# PIZ-II.net
KiCad netlist of a schematic drawn in EAGLE
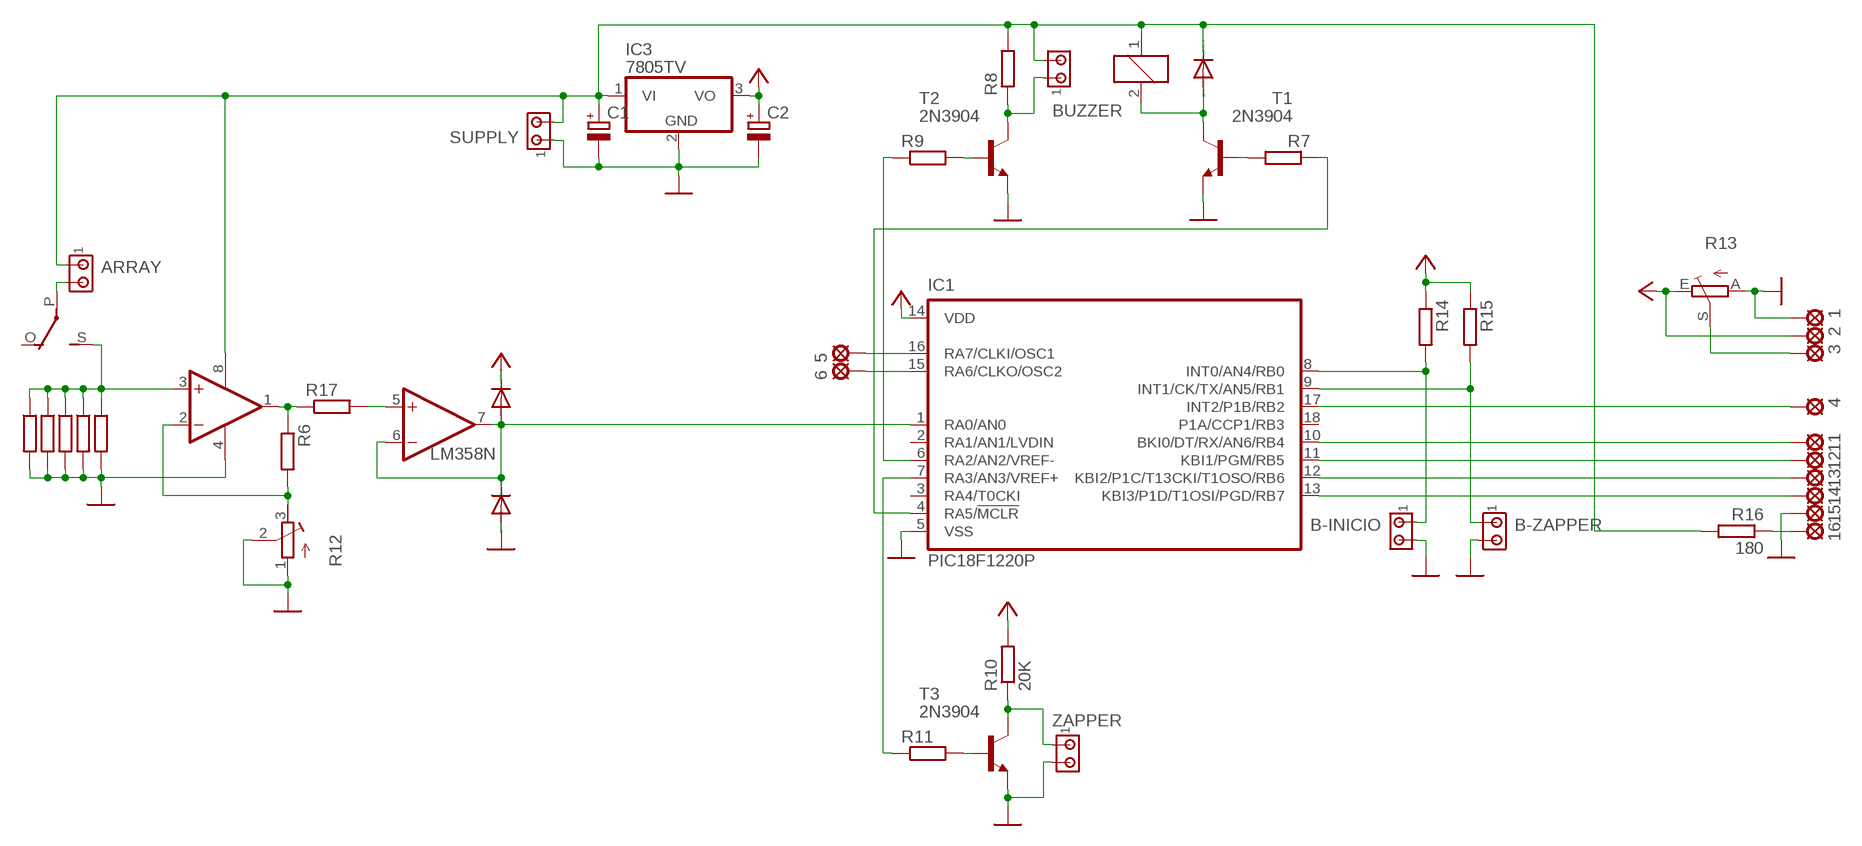
[diagram p0: schematic, sheet 1]

(export (version "E")
  (design (tool "Eeschema 10.0.6"))
  (components
    (comp (ref "1")
      (value "LSP10")
      (footprint "eagle-import:LSP10")
      (libsource (lib "eagle-import") (part "LSP10"))
    )
    (comp (ref "2")
      (value "LSP10")
      (footprint "eagle-import:LSP10")
      (libsource (lib "eagle-import") (part "LSP10"))
    )
    (comp (ref "3")
      (value "LSP10")
      (footprint "eagle-import:LSP10")
      (libsource (lib "eagle-import") (part "LSP10"))
    )
    (comp (ref "4")
      (value "LSP10")
      (footprint "eagle-import:LSP10")
      (libsource (lib "eagle-import") (part "LSP10"))
    )
    (comp (ref "5")
      (value "LSP10")
      (footprint "eagle-import:LSP10")
      (libsource (lib "eagle-import") (part "LSP10"))
    )
    (comp (ref "6")
      (value "LSP10")
      (footprint "eagle-import:LSP10")
      (libsource (lib "eagle-import") (part "LSP10"))
    )
    (comp (ref "11")
      (value "LSP10")
      (footprint "eagle-import:LSP10")
      (libsource (lib "eagle-import") (part "LSP10"))
    )
    (comp (ref "12")
      (value "LSP10")
      (footprint "eagle-import:LSP10")
      (libsource (lib "eagle-import") (part "LSP10"))
    )
    (comp (ref "13")
      (value "LSP10")
      (footprint "eagle-import:LSP10")
      (libsource (lib "eagle-import") (part "LSP10"))
    )
    (comp (ref "14")
      (value "LSP10")
      (footprint "eagle-import:LSP10")
      (libsource (lib "eagle-import") (part "LSP10"))
    )
    (comp (ref "15")
      (value "LSP10")
      (footprint "eagle-import:LSP10")
      (libsource (lib "eagle-import") (part "LSP10"))
    )
    (comp (ref "16")
      (value "LSP10")
      (footprint "eagle-import:LSP10")
      (libsource (lib "eagle-import") (part "LSP10"))
    )
    (comp (ref "ARRAY")
      (value "MTA02-100")
      (footprint "eagle-import:10X02MTA")
      (libsource (lib "eagle-import") (part "MTA02-100"))
    )
    (comp (ref "B-INICIO")
      (value "MTA02-100")
      (footprint "eagle-import:10X02MTA")
      (libsource (lib "eagle-import") (part "MTA02-100"))
    )
    (comp (ref "B-ZAPPER")
      (value "MTA02-100")
      (footprint "eagle-import:10X02MTA")
      (libsource (lib "eagle-import") (part "MTA02-100"))
    )
    (comp (ref "BUZZER")
      (value "MTA02-100")
      (footprint "eagle-import:10X02MTA")
      (libsource (lib "eagle-import") (part "MTA02-100"))
    )
    (comp (ref "C1")
      (value "CPOL-EUE2.5-7")
      (footprint "eagle-import:E2,5-7")
      (libsource (lib "eagle-import") (part "CPOL-EUE2.5-7"))
    )
    (comp (ref "C2")
      (value "CPOL-EUE2.5-7")
      (footprint "eagle-import:E2,5-7")
      (libsource (lib "eagle-import") (part "CPOL-EUE2.5-7"))
    )
    (comp (ref "D1")
      (value "1N4148DO35-7")
      (footprint "eagle-import:DO35-7")
      (libsource (lib "eagle-import") (part "1N4148DO35-7"))
    )
    (comp (ref "D2")
      (value "1N4148DO35-7")
      (footprint "eagle-import:DO35-7")
      (libsource (lib "eagle-import") (part "1N4148DO35-7"))
    )
    (comp (ref "D3")
      (value "1N4148DO35-7")
      (footprint "eagle-import:DO35-7")
      (libsource (lib "eagle-import") (part "1N4148DO35-7"))
    )
    (comp (ref "IC1")
      (value "PIC18F1220P")
      (footprint "eagle-import:DIL18")
      (fields (field (name "MF") "MICROCHIP") (field (name "MPN") "PIC18F1220-I/P"))
      (libsource (lib "eagle-import") (part "PIC18F120P2"))
    )
    (comp (ref "IC2")
      (value "LM358N")
      (footprint "eagle-import:DIL08")
      (libsource (lib "eagle-import") (part "LM358N"))
    )
    (comp (ref "IC3")
      (value "7805TV")
      (footprint "eagle-import:TO220V")
      (libsource (lib "eagle-import") (part "78TV05"))
    )
    (comp (ref "K1")
      (value "G5L")
      (footprint "eagle-import:G5LE")
      (libsource (lib "eagle-import") (part "G5L"))
    )
    (comp (ref "R1")
      (value "R-EU_0204/7")
      (footprint "eagle-import:0204_7")
      (libsource (lib "eagle-import") (part "R-EU_0204/7"))
    )
    (comp (ref "R2")
      (value "R-EU_0204/7")
      (footprint "eagle-import:0204_7")
      (libsource (lib "eagle-import") (part "R-EU_0204/7"))
    )
    (comp (ref "R3")
      (value "R-EU_0204/7")
      (footprint "eagle-import:0204_7")
      (libsource (lib "eagle-import") (part "R-EU_0204/7"))
    )
    (comp (ref "R4")
      (value "R-EU_0204/7")
      (footprint "eagle-import:0204_7")
      (libsource (lib "eagle-import") (part "R-EU_0204/7"))
    )
    (comp (ref "R5")
      (value "R-EU_0204/7")
      (footprint "eagle-import:0204_7")
      (libsource (lib "eagle-import") (part "R-EU_0204/7"))
    )
    (comp (ref "R6")
      (value "R-EU_0204/7")
      (footprint "eagle-import:0204_7")
      (libsource (lib "eagle-import") (part "R-EU_0204/7"))
    )
    (comp (ref "R7")
      (value "R-EU_0204/7")
      (footprint "eagle-import:0204_7")
      (libsource (lib "eagle-import") (part "R-EU_0204/7"))
    )
    (comp (ref "R8")
      (value "R-EU_0204/7")
      (footprint "eagle-import:0204_7")
      (libsource (lib "eagle-import") (part "R-EU_0204/7"))
    )
    (comp (ref "R9")
      (value "R-EU_0204/7")
      (footprint "eagle-import:0204_7")
      (libsource (lib "eagle-import") (part "R-EU_0204/7"))
    )
    (comp (ref "R10")
      (value "20K")
      (footprint "eagle-import:0204_7")
      (libsource (lib "eagle-import") (part "R-EU_0204/7"))
    )
    (comp (ref "R11")
      (value "R-EU_0204/7")
      (footprint "eagle-import:0204_7")
      (libsource (lib "eagle-import") (part "R-EU_0204/7"))
    )
    (comp (ref "R12")
      (value "R-TRIMM64W")
      (footprint "eagle-import:RTRIM64W")
      (libsource (lib "eagle-import") (part "R-TRIMM64W"))
    )
    (comp (ref "R13")
      (value "TRIM_EU-CA6V")
      (footprint "eagle-import:CA6V")
      (libsource (lib "eagle-import") (part "TRIM_EU-CA6V"))
    )
    (comp (ref "R14")
      (value "R-EU_0204/7")
      (footprint "eagle-import:0204_7")
      (libsource (lib "eagle-import") (part "R-EU_0204/7"))
    )
    (comp (ref "R15")
      (value "R-EU_0204/7")
      (footprint "eagle-import:0204_7")
      (libsource (lib "eagle-import") (part "R-EU_0204/7"))
    )
    (comp (ref "R16")
      (value "180")
      (footprint "eagle-import:0204_7")
      (libsource (lib "eagle-import") (part "R-EU_0204/7"))
    )
    (comp (ref "R17")
      (value "R-EU_0204/7")
      (footprint "eagle-import:0204_7")
      (libsource (lib "eagle-import") (part "R-EU_0204/7"))
    )
    (comp (ref "SUPPLY")
      (value "MTA02-100")
      (footprint "eagle-import:10X02MTA")
      (libsource (lib "eagle-import") (part "MTA02-100"))
    )
    (comp (ref "T1")
      (value "2N3904")
      (footprint "eagle-import:TO92")
      (libsource (lib "eagle-import") (part "2N3904"))
    )
    (comp (ref "T2")
      (value "2N3904")
      (footprint "eagle-import:TO92")
      (libsource (lib "eagle-import") (part "2N3904"))
    )
    (comp (ref "T3")
      (value "2N3904")
      (footprint "eagle-import:TO92")
      (libsource (lib "eagle-import") (part "2N3904"))
    )
    (comp (ref "ZAPPER")
      (value "MTA02-100")
      (footprint "eagle-import:10X02MTA")
      (libsource (lib "eagle-import") (part "MTA02-100"))
    )
  )
  (nets
    (net (code "1") (name "GND") (class "Default")
      (node (ref "1") (pin "MP") (pinfunction "MP_MP") (pintype "passive"))
      (node (ref "15") (pin "MP") (pinfunction "MP_MP") (pintype "passive"))
      (node (ref "B-INICIO") (pin "2") (pinfunction "2_2") (pintype "passive"))
      (node (ref "B-ZAPPER") (pin "2") (pinfunction "2_2") (pintype "passive"))
      (node (ref "C1") (pin "-") (pinfunction "-_-") (pintype "passive"))
      (node (ref "C2") (pin "-") (pinfunction "-_-") (pintype "passive"))
      (node (ref "D2") (pin "A") (pinfunction "A_A") (pintype "passive"))
      (node (ref "IC1") (pin "5") (pinfunction "VSS_5") (pintype "power_in"))
      (node (ref "IC2") (pin "4") (pinfunction "V-_4") (pintype "power_in"))
      (node (ref "IC3") (pin "2") (pinfunction "GND_2") (pintype "passive"))
      (node (ref "R1") (pin "2") (pinfunction "2_2") (pintype "passive"))
      (node (ref "R12") (pin "1") (pinfunction "A_1") (pintype "passive"))
      (node (ref "R12") (pin "2") (pinfunction "S_2") (pintype "passive"))
      (node (ref "R13") (pin "A") (pinfunction "A_A") (pintype "passive"))
      (node (ref "R2") (pin "2") (pinfunction "2_2") (pintype "passive"))
      (node (ref "R3") (pin "2") (pinfunction "2_2") (pintype "passive"))
      (node (ref "R4") (pin "2") (pinfunction "2_2") (pintype "passive"))
      (node (ref "R5") (pin "2") (pinfunction "2_2") (pintype "passive"))
      (node (ref "SUPPLY") (pin "1") (pinfunction "1_1") (pintype "passive"))
      (node (ref "T1") (pin "3") (pinfunction "E_3") (pintype "passive"))
      (node (ref "T2") (pin "3") (pinfunction "E_3") (pintype "passive"))
      (node (ref "T3") (pin "3") (pinfunction "E_3") (pintype "passive"))
      (node (ref "ZAPPER") (pin "2") (pinfunction "2_2") (pintype "passive"))
    )
    (net (code "2") (name "Net-(3-PadMP)") (class "Default")
      (node (ref "3") (pin "MP") (pinfunction "MP_MP") (pintype "passive"))
      (node (ref "R13") (pin "S") (pinfunction "S_S") (pintype "passive"))
    )
    (net (code "3") (name "Net-(16-PadMP)") (class "Default")
      (node (ref "16") (pin "MP") (pinfunction "MP_MP") (pintype "passive"))
      (node (ref "R16") (pin "1") (pinfunction "1_1") (pintype "passive"))
    )
    (net (code "4") (name "Net-(ARRAY-Pad2)") (class "Default")
      (node (ref "ARRAY") (pin "2") (pinfunction "2_2") (pintype "passive"))
      (node (ref "K1") (pin "P") (pinfunction "P_P") (pintype "passive"))
    )
    (net (code "5") (name "Net-(IC1-BKI0{slash}DT{slash}RX{slash}AN6{slash}RB4)") (class "Default")
      (node (ref "11") (pin "MP") (pinfunction "MP_MP") (pintype "passive"))
      (node (ref "IC1") (pin "10") (pinfunction "BKI0/DT/RX/AN6/RB4_10") (pintype "bidirectional"))
    )
    (net (code "6") (name "Net-(IC1-INT0{slash}AN4{slash}RB0)") (class "Default")
      (node (ref "B-INICIO") (pin "1") (pinfunction "1_1") (pintype "passive"))
      (node (ref "IC1") (pin "8") (pinfunction "INT0/AN4/RB0_8") (pintype "bidirectional"))
      (node (ref "R14") (pin "2") (pinfunction "2_2") (pintype "passive"))
    )
    (net (code "7") (name "Net-(IC1-INT1{slash}CK{slash}TX{slash}AN5{slash}RB1)") (class "Default")
      (node (ref "B-ZAPPER") (pin "1") (pinfunction "1_1") (pintype "passive"))
      (node (ref "IC1") (pin "9") (pinfunction "INT1/CK/TX/AN5/RB1_9") (pintype "bidirectional"))
      (node (ref "R15") (pin "2") (pinfunction "2_2") (pintype "passive"))
    )
    (net (code "8") (name "Net-(IC1-INT2{slash}P1B{slash}RB2)") (class "Default")
      (node (ref "4") (pin "MP") (pinfunction "MP_MP") (pintype "passive"))
      (node (ref "IC1") (pin "17") (pinfunction "INT2/P1B/RB2_17") (pintype "bidirectional"))
    )
    (net (code "9") (name "Net-(IC1-KBI1{slash}PGM{slash}RB5)") (class "Default")
      (node (ref "12") (pin "MP") (pinfunction "MP_MP") (pintype "passive"))
      (node (ref "IC1") (pin "11") (pinfunction "KBI1/PGM/RB5_11") (pintype "bidirectional"))
    )
    (net (code "10") (name "Net-(IC1-KBI2{slash}P1C{slash}T13CKI{slash}T1OSO{slash}RB6)") (class "Default")
      (node (ref "13") (pin "MP") (pinfunction "MP_MP") (pintype "passive"))
      (node (ref "IC1") (pin "12") (pinfunction "KBI2/P1C/T13CKI/T1OSO/RB6_12") (pintype "bidirectional"))
    )
    (net (code "11") (name "Net-(IC1-KBI3{slash}P1D{slash}T1OSI{slash}PGD{slash}RB7)") (class "Default")
      (node (ref "14") (pin "MP") (pinfunction "MP_MP") (pintype "passive"))
      (node (ref "IC1") (pin "13") (pinfunction "KBI3/P1D/T1OSI/PGD/RB7_13") (pintype "bidirectional"))
    )
    (net (code "12") (name "Net-(IC1-RA0{slash}AN0)") (class "Default")
      (node (ref "D1") (pin "A") (pinfunction "A_A") (pintype "passive"))
      (node (ref "D2") (pin "C") (pinfunction "C_C") (pintype "passive"))
      (node (ref "IC1") (pin "1") (pinfunction "RA0/AN0_1") (pintype "bidirectional"))
      (node (ref "IC2") (pin "6") (pinfunction "-IN_6") (pintype "input"))
      (node (ref "IC2") (pin "7") (pinfunction "OUT_7") (pintype "output"))
    )
    (net (code "13") (name "Net-(IC1-RA2{slash}AN2{slash}VREF-)") (class "Default")
      (node (ref "IC1") (pin "6") (pinfunction "RA2/AN2/VREF-_6") (pintype "bidirectional"))
      (node (ref "R9") (pin "1") (pinfunction "1_1") (pintype "passive"))
    )
    (net (code "14") (name "Net-(IC1-RA3{slash}AN3{slash}VREF+)") (class "Default")
      (node (ref "IC1") (pin "7") (pinfunction "RA3/AN3/VREF+_7") (pintype "bidirectional"))
      (node (ref "R11") (pin "1") (pinfunction "1_1") (pintype "passive"))
    )
    (net (code "15") (name "Net-(IC1-RA5{slash}~{MCLR})") (class "Default")
      (node (ref "IC1") (pin "4") (pinfunction "RA5/~{MCLR}_4") (pintype "input"))
      (node (ref "R7") (pin "1") (pinfunction "1_1") (pintype "passive"))
    )
    (net (code "16") (name "Net-(IC1-RA6{slash}CLKO{slash}OSC2)") (class "Default")
      (node (ref "6") (pin "MP") (pinfunction "MP_MP") (pintype "passive"))
      (node (ref "IC1") (pin "15") (pinfunction "RA6/CLKO/OSC2_15") (pintype "bidirectional"))
    )
    (net (code "17") (name "Net-(IC1-RA7{slash}CLKI{slash}OSC1)") (class "Default")
      (node (ref "5") (pin "MP") (pinfunction "MP_MP") (pintype "passive"))
      (node (ref "IC1") (pin "16") (pinfunction "RA7/CLKI/OSC1_16") (pintype "bidirectional"))
    )
    (net (code "18") (name "Net-(IC2A-+IN)") (class "Default")
      (node (ref "IC2") (pin "3") (pinfunction "+IN_3") (pintype "input"))
      (node (ref "K1") (pin "S") (pinfunction "S_S") (pintype "passive"))
      (node (ref "R1") (pin "1") (pinfunction "1_1") (pintype "passive"))
      (node (ref "R2") (pin "1") (pinfunction "1_1") (pintype "passive"))
      (node (ref "R3") (pin "1") (pinfunction "1_1") (pintype "passive"))
      (node (ref "R4") (pin "1") (pinfunction "1_1") (pintype "passive"))
      (node (ref "R5") (pin "1") (pinfunction "1_1") (pintype "passive"))
    )
    (net (code "19") (name "Net-(IC2A--IN)") (class "Default")
      (node (ref "IC2") (pin "2") (pinfunction "-IN_2") (pintype "input"))
      (node (ref "R12") (pin "3") (pinfunction "E_3") (pintype "passive"))
      (node (ref "R6") (pin "2") (pinfunction "2_2") (pintype "passive"))
    )
    (net (code "20") (name "Net-(IC2A-OUT)") (class "Default")
      (node (ref "IC2") (pin "1") (pinfunction "OUT_1") (pintype "output"))
      (node (ref "R17") (pin "1") (pinfunction "1_1") (pintype "passive"))
      (node (ref "R6") (pin "1") (pinfunction "1_1") (pintype "passive"))
    )
    (net (code "21") (name "Net-(IC2B-+IN)") (class "Default")
      (node (ref "IC2") (pin "5") (pinfunction "+IN_5") (pintype "input"))
      (node (ref "R17") (pin "2") (pinfunction "2_2") (pintype "passive"))
    )
    (net (code "22") (name "Net-(IC2C-V+)") (class "Default")
      (node (ref "ARRAY") (pin "1") (pinfunction "1_1") (pintype "passive"))
      (node (ref "BUZZER") (pin "2") (pinfunction "2_2") (pintype "passive"))
      (node (ref "C1") (pin "+") (pinfunction "+_+") (pintype "passive"))
      (node (ref "D3") (pin "C") (pinfunction "C_C") (pintype "passive"))
      (node (ref "IC2") (pin "8") (pinfunction "V+_8") (pintype "power_in"))
      (node (ref "IC3") (pin "1") (pinfunction "VI_1") (pintype "input"))
      (node (ref "K1") (pin "1") (pinfunction "1_1") (pintype "passive"))
      (node (ref "R16") (pin "2") (pinfunction "2_2") (pintype "passive"))
      (node (ref "R8") (pin "2") (pinfunction "2_2") (pintype "passive"))
      (node (ref "SUPPLY") (pin "2") (pinfunction "2_2") (pintype "passive"))
    )
    (net (code "23") (name "Net-(T1-B)") (class "Default")
      (node (ref "R7") (pin "2") (pinfunction "2_2") (pintype "passive"))
      (node (ref "T1") (pin "2") (pinfunction "B_2") (pintype "passive"))
    )
    (net (code "24") (name "Net-(T1-C)") (class "Default")
      (node (ref "D3") (pin "A") (pinfunction "A_A") (pintype "passive"))
      (node (ref "K1") (pin "2") (pinfunction "2_2") (pintype "passive"))
      (node (ref "T1") (pin "1") (pinfunction "C_1") (pintype "passive"))
    )
    (net (code "25") (name "Net-(T2-B)") (class "Default")
      (node (ref "R9") (pin "2") (pinfunction "2_2") (pintype "passive"))
      (node (ref "T2") (pin "2") (pinfunction "B_2") (pintype "passive"))
    )
    (net (code "26") (name "Net-(T2-C)") (class "Default")
      (node (ref "BUZZER") (pin "1") (pinfunction "1_1") (pintype "passive"))
      (node (ref "R8") (pin "1") (pinfunction "1_1") (pintype "passive"))
      (node (ref "T2") (pin "1") (pinfunction "C_1") (pintype "passive"))
    )
    (net (code "27") (name "Net-(T3-B)") (class "Default")
      (node (ref "R11") (pin "2") (pinfunction "2_2") (pintype "passive"))
      (node (ref "T3") (pin "2") (pinfunction "B_2") (pintype "passive"))
    )
    (net (code "28") (name "Net-(T3-C)") (class "Default")
      (node (ref "R10") (pin "1") (pinfunction "1_1") (pintype "passive"))
      (node (ref "T3") (pin "1") (pinfunction "C_1") (pintype "passive"))
      (node (ref "ZAPPER") (pin "1") (pinfunction "1_1") (pintype "passive"))
    )
    (net (code "29") (name "VCC") (class "Default")
      (node (ref "2") (pin "MP") (pinfunction "MP_MP") (pintype "passive"))
      (node (ref "C2") (pin "+") (pinfunction "+_+") (pintype "passive"))
      (node (ref "D1") (pin "C") (pinfunction "C_C") (pintype "passive"))
      (node (ref "IC1") (pin "14") (pinfunction "VDD_14") (pintype "power_in"))
      (node (ref "IC3") (pin "3") (pinfunction "VO_3") (pintype "passive"))
      (node (ref "R10") (pin "2") (pinfunction "2_2") (pintype "passive"))
      (node (ref "R13") (pin "E") (pinfunction "E_E") (pintype "passive"))
      (node (ref "R14") (pin "1") (pinfunction "1_1") (pintype "passive"))
      (node (ref "R15") (pin "1") (pinfunction "1_1") (pintype "passive"))
    )
    (net (code "30") (name "unconnected-(IC1-P1A{slash}CCP1{slash}RB3-Pad18)") (class "Default")
      (node (ref "IC1") (pin "18") (pinfunction "P1A/CCP1/RB3_18") (pintype "bidirectional"))
    )
    (net (code "31") (name "unconnected-(IC1-RA1{slash}AN1{slash}LVDIN-Pad2)") (class "Default")
      (node (ref "IC1") (pin "2") (pinfunction "RA1/AN1/LVDIN_2") (pintype "bidirectional"))
    )
    (net (code "32") (name "unconnected-(IC1-RA4{slash}T0CKI-Pad3)") (class "Default")
      (node (ref "IC1") (pin "3") (pinfunction "RA4/T0CKI_3") (pintype "bidirectional"))
    )
    (net (code "33") (name "unconnected-(K1-PadO)") (class "Default")
      (node (ref "K1") (pin "O") (pinfunction "O_O") (pintype "passive"))
    )
  )
)
